# Test2.net
KiCad netlist of a schematic drawn in EAGLE
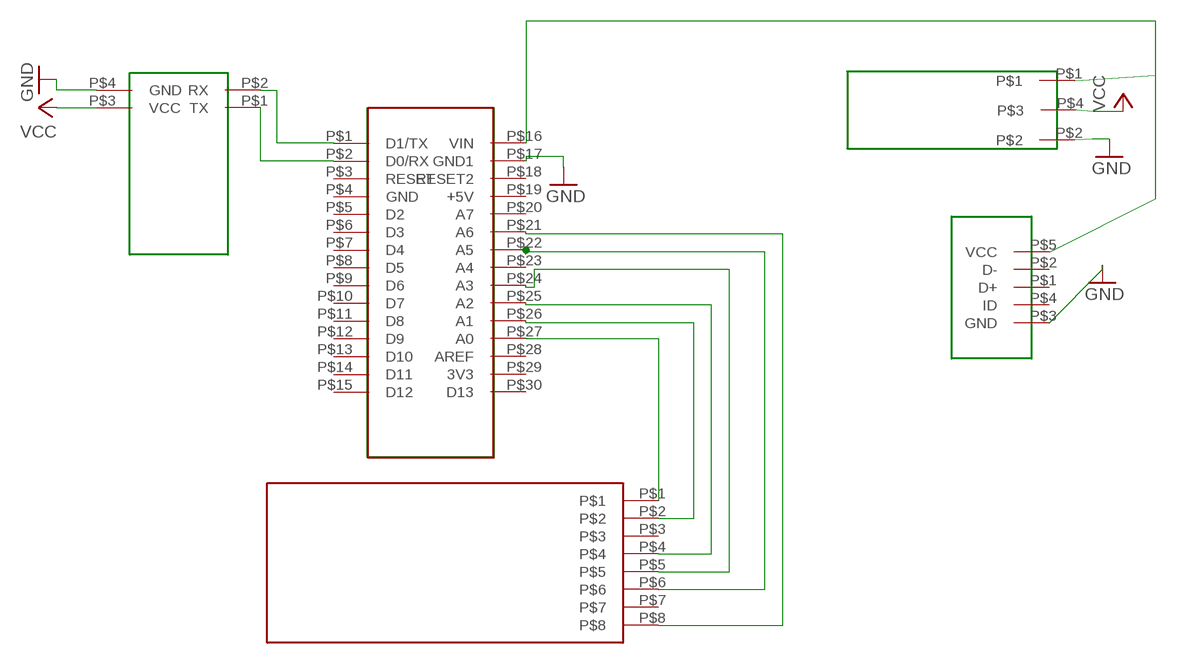
[diagram p0: schematic, sheet 1]

(export (version "E")
  (design (tool "Eeschema 10.0.6"))
  (components
    (comp (ref "U$1")
      (value "LEDARRAYLEDARRAY")
      (footprint "eagle-import:LEDARRAY")
      (libsource (lib "eagle-import") (part "LEDARRAYLEDARRAY"))
    )
    (comp (ref "U$2")
      (value "ARDUINONANOARDUINONAONO")
      (footprint "eagle-import:ARDUINONANO")
      (libsource (lib "eagle-import") (part "ARDUINONANOARDUINONAONO"))
    )
    (comp (ref "U$5")
      (value "LMC3V3LMC3V3")
      (footprint "eagle-import:LMC3V3")
      (libsource (lib "eagle-import") (part "LMC3V3LMC3V3"))
    )
    (comp (ref "U$6")
      (value "RN41RN41")
      (footprint "eagle-import:RN41")
      (libsource (lib "eagle-import") (part "RN41RN41"))
    )
    (comp (ref "U$7")
      (value "USBUSB")
      (footprint "eagle-import:USB")
      (libsource (lib "eagle-import") (part "USBUSB"))
    )
  )
  (nets
    (net (code "1") (name "GND") (class "Default")
      (node (ref "U$2") (pin "P$17") (pinfunction "GND1_P$17") (pintype "bidirectional"))
      (node (ref "U$5") (pin "P$2") (pinfunction "P$2_P$2") (pintype "bidirectional"))
      (node (ref "U$6") (pin "P$4") (pinfunction "GND_P$4") (pintype "bidirectional"))
      (node (ref "U$7") (pin "P$3") (pinfunction "GND_P$3") (pintype "bidirectional"))
    )
    (net (code "2") (name "Net-(U$2-A0)") (class "Default")
      (node (ref "U$1") (pin "P$1") (pinfunction "P$1_P$1") (pintype "bidirectional"))
      (node (ref "U$2") (pin "P$27") (pinfunction "A0_P$27") (pintype "bidirectional"))
    )
    (net (code "3") (name "Net-(U$2-A1)") (class "Default")
      (node (ref "U$1") (pin "P$2") (pinfunction "P$2_P$2") (pintype "bidirectional"))
      (node (ref "U$2") (pin "P$26") (pinfunction "A1_P$26") (pintype "bidirectional"))
    )
    (net (code "4") (name "Net-(U$2-A2)") (class "Default")
      (node (ref "U$1") (pin "P$4") (pinfunction "P$4_P$4") (pintype "bidirectional"))
      (node (ref "U$2") (pin "P$25") (pinfunction "A2_P$25") (pintype "bidirectional"))
    )
    (net (code "5") (name "Net-(U$2-A3)") (class "Default")
      (node (ref "U$1") (pin "P$5") (pinfunction "P$5_P$5") (pintype "bidirectional"))
      (node (ref "U$2") (pin "P$24") (pinfunction "A3_P$24") (pintype "bidirectional"))
    )
    (net (code "6") (name "Net-(U$2-A5)") (class "Default")
      (node (ref "U$1") (pin "P$6") (pinfunction "P$6_P$6") (pintype "bidirectional"))
      (node (ref "U$2") (pin "P$22") (pinfunction "A5_P$22") (pintype "bidirectional"))
    )
    (net (code "7") (name "Net-(U$2-A6)") (class "Default")
      (node (ref "U$1") (pin "P$8") (pinfunction "P$8_P$8") (pintype "bidirectional"))
      (node (ref "U$2") (pin "P$21") (pinfunction "A6_P$21") (pintype "bidirectional"))
    )
    (net (code "8") (name "Net-(U$2-D0{slash}RX)") (class "Default")
      (node (ref "U$2") (pin "P$2") (pinfunction "D0/RX_P$2") (pintype "bidirectional"))
      (node (ref "U$6") (pin "P$1") (pinfunction "TX_P$1") (pintype "bidirectional"))
    )
    (net (code "9") (name "Net-(U$2-D1{slash}TX)") (class "Default")
      (node (ref "U$2") (pin "P$1") (pinfunction "D1/TX_P$1") (pintype "bidirectional"))
      (node (ref "U$6") (pin "P$2") (pinfunction "RX_P$2") (pintype "bidirectional"))
    )
    (net (code "10") (name "Net-(U$2-VIN)") (class "Default")
      (node (ref "U$2") (pin "P$16") (pinfunction "VIN_P$16") (pintype "bidirectional"))
      (node (ref "U$5") (pin "P$1") (pinfunction "P$1_P$1") (pintype "bidirectional"))
      (node (ref "U$7") (pin "P$5") (pinfunction "VCC_P$5") (pintype "bidirectional"))
    )
    (net (code "11") (name "VCC") (class "Default")
      (node (ref "U$5") (pin "P$4") (pinfunction "P$3_P$4") (pintype "bidirectional"))
      (node (ref "U$6") (pin "P$3") (pinfunction "VCC_P$3") (pintype "bidirectional"))
    )
    (net (code "12") (name "unconnected-(U$1-PadP$3)") (class "Default")
      (node (ref "U$1") (pin "P$3") (pinfunction "P$3_P$3") (pintype "bidirectional"))
    )
    (net (code "13") (name "unconnected-(U$1-PadP$7)") (class "Default")
      (node (ref "U$1") (pin "P$7") (pinfunction "P$7_P$7") (pintype "bidirectional"))
    )
    (net (code "14") (name "unconnected-(U$2-+5V-PadP$19)") (class "Default")
      (node (ref "U$2") (pin "P$19") (pinfunction "+5V_P$19") (pintype "bidirectional"))
    )
    (net (code "15") (name "unconnected-(U$2-3V3-PadP$29)") (class "Default")
      (node (ref "U$2") (pin "P$29") (pinfunction "3V3_P$29") (pintype "bidirectional"))
    )
    (net (code "16") (name "unconnected-(U$2-A4-PadP$23)") (class "Default")
      (node (ref "U$2") (pin "P$23") (pinfunction "A4_P$23") (pintype "bidirectional"))
    )
    (net (code "17") (name "unconnected-(U$2-A7-PadP$20)") (class "Default")
      (node (ref "U$2") (pin "P$20") (pinfunction "A7_P$20") (pintype "bidirectional"))
    )
    (net (code "18") (name "unconnected-(U$2-AREF-PadP$28)") (class "Default")
      (node (ref "U$2") (pin "P$28") (pinfunction "AREF_P$28") (pintype "bidirectional"))
    )
    (net (code "19") (name "unconnected-(U$2-D2-PadP$5)") (class "Default")
      (node (ref "U$2") (pin "P$5") (pinfunction "D2_P$5") (pintype "bidirectional"))
    )
    (net (code "20") (name "unconnected-(U$2-D3-PadP$6)") (class "Default")
      (node (ref "U$2") (pin "P$6") (pinfunction "D3_P$6") (pintype "bidirectional"))
    )
    (net (code "21") (name "unconnected-(U$2-D4-PadP$7)") (class "Default")
      (node (ref "U$2") (pin "P$7") (pinfunction "D4_P$7") (pintype "bidirectional"))
    )
    (net (code "22") (name "unconnected-(U$2-D5-PadP$8)") (class "Default")
      (node (ref "U$2") (pin "P$8") (pinfunction "D5_P$8") (pintype "bidirectional"))
    )
    (net (code "23") (name "unconnected-(U$2-D6-PadP$9)") (class "Default")
      (node (ref "U$2") (pin "P$9") (pinfunction "D6_P$9") (pintype "bidirectional"))
    )
    (net (code "24") (name "unconnected-(U$2-D7-PadP$10)") (class "Default")
      (node (ref "U$2") (pin "P$10") (pinfunction "D7_P$10") (pintype "bidirectional"))
    )
    (net (code "25") (name "unconnected-(U$2-D8-PadP$11)") (class "Default")
      (node (ref "U$2") (pin "P$11") (pinfunction "D8_P$11") (pintype "bidirectional"))
    )
    (net (code "26") (name "unconnected-(U$2-D9-PadP$12)") (class "Default")
      (node (ref "U$2") (pin "P$12") (pinfunction "D9_P$12") (pintype "bidirectional"))
    )
    (net (code "27") (name "unconnected-(U$2-D10-PadP$13)") (class "Default")
      (node (ref "U$2") (pin "P$13") (pinfunction "D10_P$13") (pintype "bidirectional"))
    )
    (net (code "28") (name "unconnected-(U$2-D11-PadP$14)") (class "Default")
      (node (ref "U$2") (pin "P$14") (pinfunction "D11_P$14") (pintype "bidirectional"))
    )
    (net (code "29") (name "unconnected-(U$2-D12-PadP$15)") (class "Default")
      (node (ref "U$2") (pin "P$15") (pinfunction "D12_P$15") (pintype "bidirectional"))
    )
    (net (code "30") (name "unconnected-(U$2-D13-PadP$30)") (class "Default")
      (node (ref "U$2") (pin "P$30") (pinfunction "D13_P$30") (pintype "bidirectional"))
    )
    (net (code "31") (name "unconnected-(U$2-GND-PadP$4)") (class "Default")
      (node (ref "U$2") (pin "P$4") (pinfunction "GND_P$4") (pintype "bidirectional"))
    )
    (net (code "32") (name "unconnected-(U$2-RESET-PadP$3)") (class "Default")
      (node (ref "U$2") (pin "P$3") (pinfunction "RESET_P$3") (pintype "bidirectional"))
    )
    (net (code "33") (name "unconnected-(U$2-RESET2-PadP$18)") (class "Default")
      (node (ref "U$2") (pin "P$18") (pinfunction "RESET2_P$18") (pintype "bidirectional"))
    )
    (net (code "34") (name "unconnected-(U$7-D+-PadP$1)") (class "Default")
      (node (ref "U$7") (pin "P$1") (pinfunction "D+_P$1") (pintype "bidirectional"))
    )
    (net (code "35") (name "unconnected-(U$7-D--PadP$2)") (class "Default")
      (node (ref "U$7") (pin "P$2") (pinfunction "D-_P$2") (pintype "bidirectional"))
    )
    (net (code "36") (name "unconnected-(U$7-ID-PadP$4)") (class "Default")
      (node (ref "U$7") (pin "P$4") (pinfunction "ID_P$4") (pintype "bidirectional"))
    )
  )
)
